# HRM.net
KiCad netlist of a schematic drawn in Altium Designer
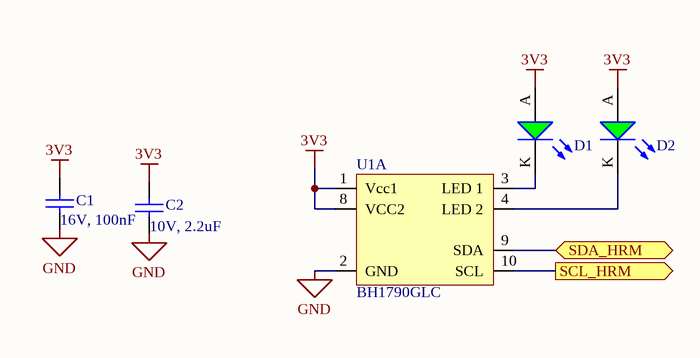
[diagram p0: HRM.SchDoc]

(export (version "E")
  (design (tool "Eeschema 10.0.6"))
  (components
    (comp (ref "C1")
      (value "16V, 100nF")
      (footprint "0603_1.6x0.8x0.8mm_Reflow Soldering")
      (description "WCAP-CSGP Ceramic Capacitors, 0603, X7R, 16V, 100nF")
      (fields (field (name "PART NUMBER") "885012206046") (field (name "PUBLISHER") "Wurth Elektronik"))
      (libsource (lib "ALTIUM-WCAP-CSGP-0603-rev17b") (part "885012206046"))
    )
    (comp (ref "C2")
      (value "10V, 2.2uF")
      (footprint "0603_1.6x0.8x0.8mm_Reflow Soldering")
      (description "WCAP-CSGP Ceramic Capacitors, 0603, X7R, 10V, 2.2uF")
      (fields (field (name "PART NUMBER") "885012206027") (field (name "PUBLISHER") "Wurth Elektronik"))
      (libsource (lib "ALTIUM-WCAP-CSGP-0603-rev17b") (part "885012206027"))
    )
    (comp (ref "D1")
      (value "Bright Green, 2V, 140°")
      (footprint "WL-SMCW_0603_150060xx75003")
      (description "WL-SMCW Mono-color Chip LED Waterclear, SMT, size 0603, Bright Green, 2V, 140°")
      (fields
        (field (name "MANUFACTURER PART NUMBER") "150060VS75003")
        (field (name "MANUFACTURER") "Wurth Elektronik")
      )
      (libsource (lib "Altium_WL-SMCW (rev22b)") (part "150060VS75003"))
    )
    (comp (ref "D2")
      (value "Bright Green, 2V, 140°")
      (footprint "WL-SMCW_0603_150060xx75003")
      (description "WL-SMCW Mono-color Chip LED Waterclear, SMT, size 0603, Bright Green, 2V, 140°")
      (fields
        (field (name "MANUFACTURER PART NUMBER") "150060VS75003")
        (field (name "MANUFACTURER") "Wurth Elektronik")
      )
      (libsource (lib "Altium_WL-SMCW (rev22b)") (part "150060VS75003"))
    )
    (comp (ref "U1")
      (value "BH1790GLC")
      (footprint "WLGA010V28_ROHM")
      (description "Optical Sensor for Heart Rate Monitor IC")
      (libsource (lib "Oblak Library") (part "BH1790GLC"))
    )
  )
  (nets
    (net (code "1") (name "/SCL_HRM") (class "Default")
      (node (ref "U1") (pin "10") (pinfunction "SCL_10") (pintype "passive"))
    )
    (net (code "2") (name "/SDA_HRM") (class "Default")
      (node (ref "U1") (pin "9") (pinfunction "SDA_9") (pintype "passive"))
    )
    (net (code "3") (name "3V3") (class "Default")
      (node (ref "C1") (pin "2") (pinfunction "2_2") (pintype "passive"))
      (node (ref "C2") (pin "2") (pinfunction "2_2") (pintype "passive"))
      (node (ref "D1") (pin "A") (pinfunction "A_A") (pintype "passive"))
      (node (ref "D2") (pin "A") (pinfunction "A_A") (pintype "passive"))
      (node (ref "U1") (pin "1") (pinfunction "Vcc1_1") (pintype "passive"))
      (node (ref "U1") (pin "8") (pinfunction "VCC2_8") (pintype "passive"))
    )
    (net (code "4") (name "GND") (class "Default")
      (node (ref "C1") (pin "1") (pinfunction "1_1") (pintype "passive"))
      (node (ref "C2") (pin "1") (pinfunction "1_1") (pintype "passive"))
      (node (ref "U1") (pin "2") (pinfunction "GND_2") (pintype "passive"))
    )
    (net (code "5") (name "Net-(U1A-LED_1)") (class "Default")
      (node (ref "D1") (pin "K") (pinfunction "K_K") (pintype "passive"))
      (node (ref "U1") (pin "3") (pinfunction "LED_1_3") (pintype "passive"))
    )
    (net (code "6") (name "Net-(U1A-LED_2)") (class "Default")
      (node (ref "D2") (pin "K") (pinfunction "K_K") (pintype "passive"))
      (node (ref "U1") (pin "4") (pinfunction "LED_2_4") (pintype "passive"))
    )
  )
)
